# LPC_LCD_V098_0.net
KiCad netlist of a schematic drawn in EAGLE
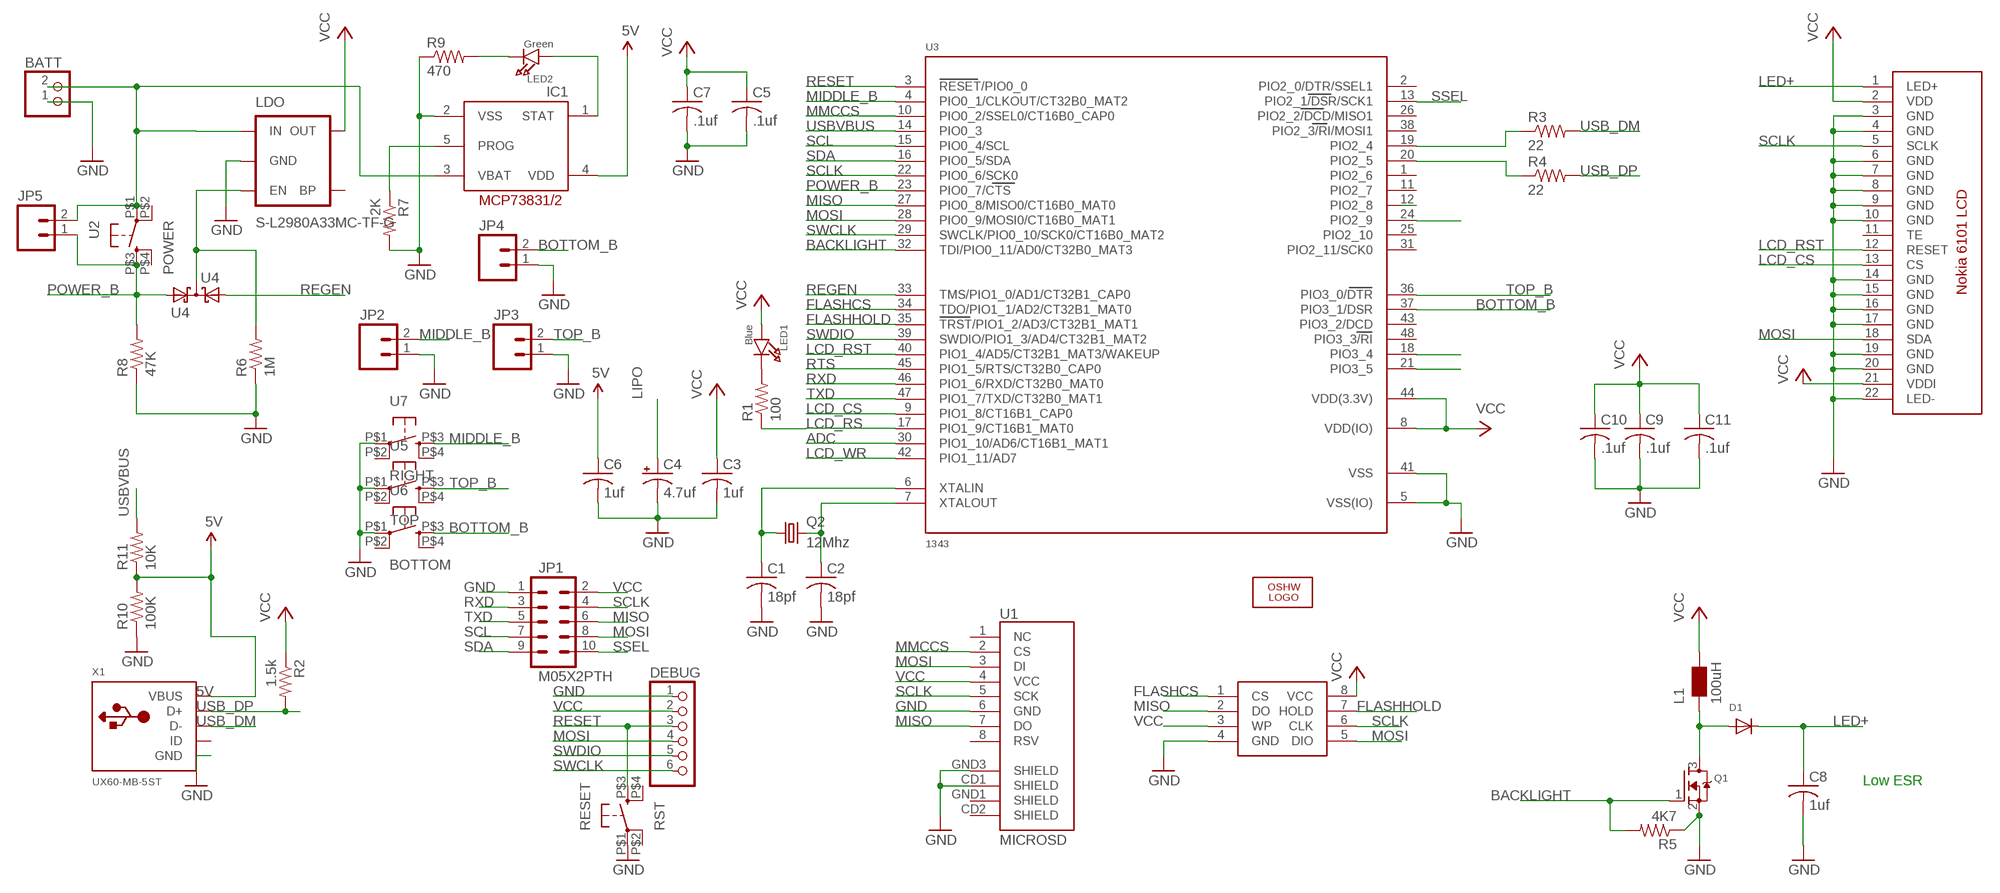
[diagram p0: schematic, sheet 1]

(export (version "E")
  (design (tool "Eeschema 10.0.6"))
  (components
    (comp (ref "BATT")
      (value "JST_2PIN-SMT")
      (footprint "eagle-import:JST-PH-2-SMT")
      (libsource (lib "eagle-import") (part "JST_2PIN-SMT"))
    )
    (comp (ref "C1")
      (value "18pf")
      (footprint "eagle-import:C0805")
      (libsource (lib "eagle-import") (part "C-USC0805"))
    )
    (comp (ref "C2")
      (value "18pf")
      (footprint "eagle-import:C0805")
      (libsource (lib "eagle-import") (part "C-USC0805"))
    )
    (comp (ref "C3")
      (value "1uf")
      (footprint "eagle-import:C0805")
      (libsource (lib "eagle-import") (part "C-USC0805"))
    )
    (comp (ref "C4")
      (value "4.7uf")
      (footprint "eagle-import:EIA3216")
      (libsource (lib "eagle-import") (part "CAP_POL1206"))
    )
    (comp (ref "C5")
      (value ".1uf")
      (footprint "eagle-import:C0805")
      (libsource (lib "eagle-import") (part "C-USC0805"))
    )
    (comp (ref "C6")
      (value "1uf")
      (footprint "eagle-import:C0805")
      (libsource (lib "eagle-import") (part "C-USC0805"))
    )
    (comp (ref "C7")
      (value ".1uf")
      (footprint "eagle-import:C0805")
      (libsource (lib "eagle-import") (part "C-USC0805"))
    )
    (comp (ref "C8")
      (value "1uf")
      (footprint "eagle-import:C0805")
      (libsource (lib "eagle-import") (part "C-USC0805"))
    )
    (comp (ref "C9")
      (value ".1uf")
      (footprint "eagle-import:C0805")
      (libsource (lib "eagle-import") (part "C-USC0805"))
    )
    (comp (ref "C10")
      (value ".1uf")
      (footprint "eagle-import:C0805")
      (libsource (lib "eagle-import") (part "C-USC0805"))
    )
    (comp (ref "C11")
      (value ".1uf")
      (footprint "eagle-import:C0805")
      (libsource (lib "eagle-import") (part "C-USC0805"))
    )
    (comp (ref "D1")
      (value "DIODESOD-123")
      (footprint "eagle-import:SOD-123")
      (libsource (lib "eagle-import") (part "DIODESOD-123"))
    )
    (comp (ref "DEBUG")
      (value "HEADER-1X6ROUND")
      (footprint "eagle-import:1X06_ROUND")
      (libsource (lib "eagle-import") (part "HEADER-1X6ROUND"))
    )
    (comp (ref "IC1")
      (value "MCP73831")
      (footprint "eagle-import:SOT23-5L")
      (libsource (lib "eagle-import") (part "MCP73831/OT"))
    )
    (comp (ref "JP1")
      (value "M05X2PTH")
      (footprint "eagle-import:AVR_ICSP")
      (libsource (lib "eagle-import") (part "M05X2PTH"))
    )
    (comp (ref "JP2")
      (value "M02LOCK")
      (footprint "eagle-import:1X02_LOCK")
      (libsource (lib "eagle-import") (part "M02LOCK"))
    )
    (comp (ref "JP3")
      (value "M02LOCK")
      (footprint "eagle-import:1X02_LOCK")
      (libsource (lib "eagle-import") (part "M02LOCK"))
    )
    (comp (ref "JP4")
      (value "M02LOCK")
      (footprint "eagle-import:1X02_LOCK")
      (libsource (lib "eagle-import") (part "M02LOCK"))
    )
    (comp (ref "JP5")
      (value "M02LOCK")
      (footprint "eagle-import:1X02_LOCK")
      (libsource (lib "eagle-import") (part "M02LOCK"))
    )
    (comp (ref "L1")
      (value "100uH")
      (footprint "eagle-import:WE-KI_1008_B")
      (libsource (lib "eagle-import") (part "WE-KIHQ_1008"))
    )
    (comp (ref "LDO")
      (value "S-L2980A33MC-TF-G")
      (footprint "eagle-import:SOT23-5")
      (libsource (lib "eagle-import") (part "V_REG_LDOSMD"))
    )
    (comp (ref "LED1")
      (value "Blue")
      (footprint "eagle-import:CHIPLED_0805")
      (libsource (lib "eagle-import") (part "LED0805"))
    )
    (comp (ref "LED2")
      (value "Green")
      (footprint "eagle-import:CHIPLED_0805")
      (libsource (lib "eagle-import") (part "LED0805"))
    )
    (comp (ref "LOGO1")
      (value "OSHW_LOGO_FILLX0350-NT")
      (footprint "eagle-import:OSHW_FILLX350_NOTEXT")
      (libsource (lib "eagle-import") (part "OSHW_LOGO_FILLX0350-NT"))
    )
    (comp (ref "Q1")
      (value "MOSFET-NREFLOW")
      (footprint "eagle-import:SOT23-R")
      (libsource (lib "eagle-import") (part "MOSFET-NREFLOW"))
    )
    (comp (ref "Q2")
      (value "12Mhz")
      (footprint "eagle-import:CRYSTAL-SMD-5X3")
      (libsource (lib "eagle-import") (part "CRYSTAL5X3"))
    )
    (comp (ref "R1")
      (value "100")
      (footprint "eagle-import:M0805")
      (libsource (lib "eagle-import") (part "R-US_M0805"))
    )
    (comp (ref "R2")
      (value "1.5k")
      (footprint "eagle-import:M0805")
      (libsource (lib "eagle-import") (part "R-US_M0805"))
    )
    (comp (ref "R3")
      (value "22")
      (footprint "eagle-import:M0805")
      (libsource (lib "eagle-import") (part "R-US_M0805"))
    )
    (comp (ref "R4")
      (value "22")
      (footprint "eagle-import:M0805")
      (libsource (lib "eagle-import") (part "R-US_M0805"))
    )
    (comp (ref "R5")
      (value "4K7")
      (footprint "eagle-import:M0805")
      (libsource (lib "eagle-import") (part "R-US_M0805"))
    )
    (comp (ref "R6")
      (value "1M")
      (footprint "eagle-import:M0805")
      (libsource (lib "eagle-import") (part "R-US_M0805"))
    )
    (comp (ref "R7")
      (value "2K")
      (footprint "eagle-import:M0805")
      (libsource (lib "eagle-import") (part "R-US_M0805"))
    )
    (comp (ref "R8")
      (value "47K")
      (footprint "eagle-import:M0805")
      (libsource (lib "eagle-import") (part "R-US_M0805"))
    )
    (comp (ref "R9")
      (value "470")
      (footprint "eagle-import:M0805")
      (libsource (lib "eagle-import") (part "R-US_M0805"))
    )
    (comp (ref "R10")
      (value "100K")
      (footprint "eagle-import:M0805")
      (libsource (lib "eagle-import") (part "R-US_M0805"))
    )
    (comp (ref "R11")
      (value "10K")
      (footprint "eagle-import:M0805")
      (libsource (lib "eagle-import") (part "R-US_M0805"))
    )
    (comp (ref "RESET")
      (value "RST")
      (footprint "eagle-import:SWITCH_KMR4")
      (libsource (lib "eagle-import") (part "SWITCH_KMR4"))
    )
    (comp (ref "U$1")
      (value "spiflash")
      (footprint "eagle-import:SOIC8")
      (libsource (lib "eagle-import") (part "SPIFLASH"))
    )
    (comp (ref "U$3")
      (value "PETERATMEGA644_NOKIA6101_LCD")
      (footprint "eagle-import:PETERATMEGA644_NOKIA6101_LCD")
      (libsource (lib "eagle-import") (part "PETERATMEGA644_NOKIA6101_LCD"))
    )
    (comp (ref "U1")
      (value "MICROSD")
      (footprint "eagle-import:MICRO-SD-SOCKET-PP")
      (libsource (lib "eagle-import") (part "USD-SOCKETNEW"))
    )
    (comp (ref "U2")
      (value "POWER")
      (footprint "eagle-import:SWITCH_KMS_WIDE")
      (libsource (lib "eagle-import") (part "KMS_SWITCHSWITCH_KMS_WIDE_HAND"))
    )
    (comp (ref "U3")
      (value "1343")
      (footprint "eagle-import:LQFP48")
      (fields (field (name "MANF") "NXP"))
      (libsource (lib "eagle-import") (part "LPC1113/4"))
    )
    (comp (ref "U4")
      (value "U4")
      (footprint "eagle-import:SOT23")
      (libsource (lib "eagle-import") (part "BAT54CWT1G"))
    )
    (comp (ref "U5")
      (value "TOP")
      (footprint "eagle-import:SWITCH_KMS_WIDE")
      (libsource (lib "eagle-import") (part "KMS_SWITCHSWITCH_KMS_WIDE_HAND"))
    )
    (comp (ref "U6")
      (value "BOTTOM")
      (footprint "eagle-import:SWITCH_KMS_WIDE")
      (libsource (lib "eagle-import") (part "KMS_SWITCHSWITCH_KMS_WIDE_HAND"))
    )
    (comp (ref "U7")
      (value "RIGHT")
      (footprint "eagle-import:SWITCH_KMS_WIDE")
      (libsource (lib "eagle-import") (part "KMS_SWITCHSWITCH_KMS_WIDE_HAND"))
    )
    (comp (ref "X1")
      (value "UX60-MB-5ST")
      (footprint "eagle-import:USB-MINIB")
      (libsource (lib "eagle-import") (part "USBMINIB"))
    )
  )
  (nets
    (net (code "1") (name "/ADC") (class "Default")
      (node (ref "U3") (pin "30") (pinfunction "PIO1_10/AD6/CT16B1_MAT1_30") (pintype "bidirectional"))
    )
    (net (code "2") (name "/BACKLIGHT") (class "Default")
      (node (ref "Q1") (pin "1") (pinfunction "G_1") (pintype "bidirectional"))
      (node (ref "R5") (pin "2") (pinfunction "2_2") (pintype "passive"))
      (node (ref "U3") (pin "32") (pinfunction "TDI/PIO0_11/AD0/CT32B0_MAT3_32") (pintype "bidirectional"))
    )
    (net (code "3") (name "/BOTTOM_B") (class "Default")
      (node (ref "JP4") (pin "2") (pinfunction "2_2") (pintype "passive"))
      (node (ref "U3") (pin "37") (pinfunction "PIO3_1/DSR_37") (pintype "bidirectional"))
      (node (ref "U6") (pin "P$3") (pinfunction "3_P$3") (pintype "passive"))
    )
    (net (code "4") (name "/FLASHCS") (class "Default")
      (node (ref "U$1") (pin "1") (pinfunction "CS_1") (pintype "bidirectional"))
      (node (ref "U3") (pin "34") (pinfunction "TDO/PIO1_1/AD2/CT32B1_MAT0_34") (pintype "bidirectional"))
    )
    (net (code "5") (name "/FLASHHOLD") (class "Default")
      (node (ref "U$1") (pin "7") (pinfunction "HOLD_7") (pintype "bidirectional"))
      (node (ref "U3") (pin "35") (pinfunction "TRST/PIO1_2/AD3/CT32B1_MAT1_35") (pintype "bidirectional"))
    )
    (net (code "6") (name "/LCD_CS") (class "Default")
      (node (ref "U$3") (pin "13") (pinfunction "CS_13") (pintype "bidirectional"))
      (node (ref "U3") (pin "9") (pinfunction "PIO1_8/CT16B1_CAP0_9") (pintype "bidirectional"))
    )
    (net (code "7") (name "/LCD_RS") (class "Default")
      (node (ref "R1") (pin "1") (pinfunction "1_1") (pintype "passive"))
      (node (ref "U3") (pin "17") (pinfunction "PIO1_9/CT16B1_MAT0_17") (pintype "bidirectional"))
    )
    (net (code "8") (name "/LCD_RST") (class "Default")
      (node (ref "U$3") (pin "12") (pinfunction "RESET_12") (pintype "bidirectional"))
      (node (ref "U3") (pin "40") (pinfunction "PIO1_4/AD5/CT32B1_MAT3/WAKEUP_40") (pintype "bidirectional"))
    )
    (net (code "9") (name "/LCD_WR") (class "Default")
      (node (ref "U3") (pin "42") (pinfunction "PIO1_11/AD7_42") (pintype "bidirectional"))
    )
    (net (code "10") (name "/LED+") (class "Default")
      (node (ref "C8") (pin "1") (pinfunction "1_1") (pintype "passive"))
      (node (ref "D1") (pin "C") (pinfunction "C_C") (pintype "passive"))
      (node (ref "U$3") (pin "1") (pinfunction "LED+_1") (pintype "bidirectional"))
    )
    (net (code "11") (name "/LIPO") (class "Default")
      (node (ref "BATT") (pin "2") (pinfunction "1_2") (pintype "passive"))
      (node (ref "C4") (pin "A") (pinfunction "+_A") (pintype "passive"))
      (node (ref "IC1") (pin "3") (pinfunction "VBAT_3") (pintype "bidirectional"))
      (node (ref "JP5") (pin "2") (pinfunction "2_2") (pintype "passive"))
      (node (ref "LDO") (pin "1") (pinfunction "IN_1") (pintype "input"))
      (node (ref "U2") (pin "P$1") (pinfunction "1_P$1") (pintype "passive"))
    )
    (net (code "12") (name "/MIDDLE_B") (class "Default")
      (node (ref "JP2") (pin "2") (pinfunction "2_2") (pintype "passive"))
      (node (ref "U3") (pin "4") (pinfunction "PIO0_1/CLKOUT/CT32B0_MAT2_4") (pintype "bidirectional"))
      (node (ref "U7") (pin "P$3") (pinfunction "3_P$3") (pintype "passive"))
    )
    (net (code "13") (name "/MISO") (class "Default")
      (node (ref "JP1") (pin "6") (pinfunction "6_6") (pintype "passive"))
      (node (ref "U$1") (pin "2") (pinfunction "DO_2") (pintype "bidirectional"))
      (node (ref "U1") (pin "7") (pinfunction "DO_7") (pintype "bidirectional"))
      (node (ref "U3") (pin "27") (pinfunction "PIO0_8/MISO0/CT16B0_MAT0_27") (pintype "bidirectional"))
    )
    (net (code "14") (name "/MMCCS") (class "Default")
      (node (ref "U1") (pin "2") (pinfunction "CS_2") (pintype "bidirectional"))
      (node (ref "U3") (pin "10") (pinfunction "PIO0_2/SSEL0/CT16B0_CAP0_10") (pintype "bidirectional"))
    )
    (net (code "15") (name "/MOSI") (class "Default")
      (node (ref "DEBUG") (pin "4") (pinfunction "4_4") (pintype "passive"))
      (node (ref "JP1") (pin "8") (pinfunction "8_8") (pintype "passive"))
      (node (ref "U$1") (pin "5") (pinfunction "DIO_5") (pintype "bidirectional"))
      (node (ref "U$3") (pin "18") (pinfunction "SDA_18") (pintype "bidirectional"))
      (node (ref "U1") (pin "3") (pinfunction "DI_3") (pintype "bidirectional"))
      (node (ref "U3") (pin "28") (pinfunction "PIO0_9/MOSI0/CT16B0_MAT1_28") (pintype "bidirectional"))
    )
    (net (code "16") (name "/POWER_B") (class "Default")
      (node (ref "JP5") (pin "1") (pinfunction "1_1") (pintype "passive"))
      (node (ref "R8") (pin "2") (pinfunction "2_2") (pintype "passive"))
      (node (ref "U2") (pin "P$3") (pinfunction "3_P$3") (pintype "passive"))
      (node (ref "U3") (pin "23") (pinfunction "PIO0_7/CTS_23") (pintype "bidirectional"))
      (node (ref "U4") (pin "2") (pinfunction "K1_2") (pintype "passive"))
    )
    (net (code "17") (name "/REGEN") (class "Default")
      (node (ref "U3") (pin "33") (pinfunction "TMS/PIO1_0/AD1/CT32B1_CAP0_33") (pintype "bidirectional"))
      (node (ref "U4") (pin "1") (pinfunction "K2_1") (pintype "passive"))
    )
    (net (code "18") (name "/RESET") (class "Default")
      (node (ref "DEBUG") (pin "3") (pinfunction "3_3") (pintype "passive"))
      (node (ref "RESET") (pin "P$3") (pinfunction "3_P$3") (pintype "passive"))
      (node (ref "U3") (pin "3") (pinfunction "RESET/PIO0_0_3") (pintype "bidirectional"))
    )
    (net (code "19") (name "/RTS") (class "Default")
      (node (ref "U3") (pin "45") (pinfunction "PIO1_5/RTS/CT32B0_CAP0_45") (pintype "bidirectional"))
    )
    (net (code "20") (name "/RXD") (class "Default")
      (node (ref "JP1") (pin "3") (pinfunction "3_3") (pintype "passive"))
      (node (ref "U3") (pin "46") (pinfunction "PIO1_6/RXD/CT32B0_MAT0_46") (pintype "bidirectional"))
    )
    (net (code "21") (name "/SCL") (class "Default")
      (node (ref "JP1") (pin "7") (pinfunction "7_7") (pintype "passive"))
      (node (ref "U3") (pin "15") (pinfunction "PIO0_4/SCL_15") (pintype "bidirectional"))
    )
    (net (code "22") (name "/SCLK") (class "Default")
      (node (ref "JP1") (pin "4") (pinfunction "4_4") (pintype "passive"))
      (node (ref "U$1") (pin "6") (pinfunction "CLK_6") (pintype "bidirectional"))
      (node (ref "U$3") (pin "5") (pinfunction "SCLK_5") (pintype "bidirectional"))
      (node (ref "U1") (pin "5") (pinfunction "SCK_5") (pintype "bidirectional"))
      (node (ref "U3") (pin "22") (pinfunction "PIO0_6/SCK0_22") (pintype "bidirectional"))
    )
    (net (code "23") (name "/SDA") (class "Default")
      (node (ref "JP1") (pin "9") (pinfunction "9_9") (pintype "passive"))
      (node (ref "U3") (pin "16") (pinfunction "PIO0_5/SDA_16") (pintype "bidirectional"))
    )
    (net (code "24") (name "/SSEL") (class "Default")
      (node (ref "JP1") (pin "10") (pinfunction "10_10") (pintype "passive"))
      (node (ref "U3") (pin "13") (pinfunction "PIO2_1/DSR/SCK1_13") (pintype "bidirectional"))
    )
    (net (code "25") (name "/SWCLK") (class "Default")
      (node (ref "DEBUG") (pin "6") (pinfunction "6_6") (pintype "passive"))
      (node (ref "U3") (pin "29") (pinfunction "SWCLK/PIO0_10/SCK0/CT16B0_MAT2_29") (pintype "bidirectional"))
    )
    (net (code "26") (name "/SWDIO") (class "Default")
      (node (ref "DEBUG") (pin "5") (pinfunction "5_5") (pintype "passive"))
      (node (ref "U3") (pin "39") (pinfunction "SWDIO/PIO1_3/AD4/CT32B1_MAT2_39") (pintype "bidirectional"))
    )
    (net (code "27") (name "/TOP_B") (class "Default")
      (node (ref "JP3") (pin "2") (pinfunction "2_2") (pintype "passive"))
      (node (ref "U3") (pin "36") (pinfunction "PIO3_0/DTR_36") (pintype "bidirectional"))
      (node (ref "U5") (pin "P$3") (pinfunction "3_P$3") (pintype "passive"))
    )
    (net (code "28") (name "/TXD") (class "Default")
      (node (ref "JP1") (pin "5") (pinfunction "5_5") (pintype "passive"))
      (node (ref "U3") (pin "47") (pinfunction "PIO1_7/TXD/CT32B0_MAT1_47") (pintype "bidirectional"))
    )
    (net (code "29") (name "/USBVBUS") (class "Default")
      (node (ref "R11") (pin "2") (pinfunction "2_2") (pintype "passive"))
      (node (ref "U3") (pin "14") (pinfunction "PIO0_3_14") (pintype "bidirectional"))
    )
    (net (code "30") (name "/USB_DM") (class "Default")
      (node (ref "R3") (pin "2") (pinfunction "2_2") (pintype "passive"))
      (node (ref "X1") (pin "D-") (pinfunction "D-_D-") (pintype "bidirectional"))
    )
    (net (code "31") (name "/USB_DP") (class "Default")
      (node (ref "R2") (pin "2") (pinfunction "2_2") (pintype "passive"))
      (node (ref "R4") (pin "2") (pinfunction "2_2") (pintype "passive"))
      (node (ref "X1") (pin "D+") (pinfunction "D+_D+") (pintype "bidirectional"))
    )
    (net (code "32") (name "5V") (class "Default")
      (node (ref "C6") (pin "1") (pinfunction "1_1") (pintype "passive"))
      (node (ref "IC1") (pin "4") (pinfunction "VDD_4") (pintype "power_in"))
      (node (ref "R10") (pin "2") (pinfunction "2_2") (pintype "passive"))
      (node (ref "R11") (pin "1") (pinfunction "1_1") (pintype "passive"))
      (node (ref "X1") (pin "VBUS") (pinfunction "VBUS_VBUS") (pintype "power_in"))
    )
    (net (code "33") (name "GND") (class "Default")
      (node (ref "BATT") (pin "1") (pinfunction "2_1") (pintype "passive"))
      (node (ref "C1") (pin "2") (pinfunction "2_2") (pintype "passive"))
      (node (ref "C10") (pin "2") (pinfunction "2_2") (pintype "passive"))
      (node (ref "C11") (pin "2") (pinfunction "2_2") (pintype "passive"))
      (node (ref "C2") (pin "2") (pinfunction "2_2") (pintype "passive"))
      (node (ref "C3") (pin "2") (pinfunction "2_2") (pintype "passive"))
      (node (ref "C4") (pin "C") (pinfunction "-_C") (pintype "passive"))
      (node (ref "C5") (pin "2") (pinfunction "2_2") (pintype "passive"))
      (node (ref "C6") (pin "2") (pinfunction "2_2") (pintype "passive"))
      (node (ref "C7") (pin "2") (pinfunction "2_2") (pintype "passive"))
      (node (ref "C8") (pin "2") (pinfunction "2_2") (pintype "passive"))
      (node (ref "C9") (pin "2") (pinfunction "2_2") (pintype "passive"))
      (node (ref "DEBUG") (pin "1") (pinfunction "1_1") (pintype "passive"))
      (node (ref "IC1") (pin "2") (pinfunction "VSS_2") (pintype "power_in"))
      (node (ref "JP1") (pin "1") (pinfunction "1_1") (pintype "passive"))
      (node (ref "JP2") (pin "1") (pinfunction "1_1") (pintype "passive"))
      (node (ref "JP3") (pin "1") (pinfunction "1_1") (pintype "passive"))
      (node (ref "JP4") (pin "1") (pinfunction "1_1") (pintype "passive"))
      (node (ref "LDO") (pin "2") (pinfunction "GND_2") (pintype "input"))
      (node (ref "Q1") (pin "2") (pinfunction "S_2") (pintype "bidirectional"))
      (node (ref "R10") (pin "1") (pinfunction "1_1") (pintype "passive"))
      (node (ref "R5") (pin "1") (pinfunction "1_1") (pintype "passive"))
      (node (ref "R6") (pin "1") (pinfunction "1_1") (pintype "passive"))
      (node (ref "R7") (pin "2") (pinfunction "2_2") (pintype "passive"))
      (node (ref "R8") (pin "1") (pinfunction "1_1") (pintype "passive"))
      (node (ref "R9") (pin "1") (pinfunction "1_1") (pintype "passive"))
      (node (ref "RESET") (pin "P$1") (pinfunction "1_P$1") (pintype "passive"))
      (node (ref "U$1") (pin "4") (pinfunction "GND_4") (pintype "bidirectional"))
      (node (ref "U$3") (pin "10") (pinfunction "GND_10") (pintype "bidirectional"))
      (node (ref "U$3") (pin "14") (pinfunction "GND_14") (pintype "bidirectional"))
      (node (ref "U$3") (pin "15") (pinfunction "GND_15") (pintype "bidirectional"))
      (node (ref "U$3") (pin "16") (pinfunction "GND_16") (pintype "bidirectional"))
      (node (ref "U$3") (pin "17") (pinfunction "GND_17") (pintype "bidirectional"))
      (node (ref "U$3") (pin "19") (pinfunction "GND_19") (pintype "bidirectional"))
      (node (ref "U$3") (pin "20") (pinfunction "GND_20") (pintype "bidirectional"))
      (node (ref "U$3") (pin "22") (pinfunction "LED-_22") (pintype "bidirectional"))
      (node (ref "U$3") (pin "3") (pinfunction "GND_3") (pintype "bidirectional"))
      (node (ref "U$3") (pin "4") (pinfunction "GND_4") (pintype "bidirectional"))
      (node (ref "U$3") (pin "6") (pinfunction "GND_6") (pintype "bidirectional"))
      (node (ref "U$3") (pin "7") (pinfunction "GND_7") (pintype "bidirectional"))
      (node (ref "U$3") (pin "8") (pinfunction "GND_8") (pintype "bidirectional"))
      (node (ref "U$3") (pin "9") (pinfunction "GND_9") (pintype "bidirectional"))
      (node (ref "U1") (pin "6") (pinfunction "GND_6") (pintype "bidirectional"))
      (node (ref "U1") (pin "CD1") (pinfunction "SHIELD_CD1") (pintype "bidirectional"))
      (node (ref "U1") (pin "GND3") (pinfunction "SHIELD_GND3") (pintype "bidirectional"))
      (node (ref "U3") (pin "41") (pinfunction "VSS_41") (pintype "power_in"))
      (node (ref "U3") (pin "5") (pinfunction "VSS(IO)_5") (pintype "power_in"))
      (node (ref "U5") (pin "P$1") (pinfunction "1_P$1") (pintype "passive"))
      (node (ref "U6") (pin "P$1") (pinfunction "1_P$1") (pintype "passive"))
      (node (ref "U7") (pin "P$1") (pinfunction "1_P$1") (pintype "passive"))
      (node (ref "X1") (pin "GND") (pinfunction "GND_GND") (pintype "power_in"))
    )
    (net (code "34") (name "Net-(IC1-PROG)") (class "Default")
      (node (ref "IC1") (pin "5") (pinfunction "PROG_5") (pintype "input"))
      (node (ref "R7") (pin "1") (pinfunction "1_1") (pintype "passive"))
    )
    (net (code "35") (name "Net-(IC1-STAT)") (class "Default")
      (node (ref "IC1") (pin "1") (pinfunction "STAT_1") (pintype "output"))
      (node (ref "LED2") (pin "A") (pinfunction "A_A") (pintype "passive"))
    )
    (net (code "36") (name "Net-(L1-1)") (class "Default")
      (node (ref "D1") (pin "A") (pinfunction "A_A") (pintype "passive"))
      (node (ref "L1") (pin "2") (pinfunction "1_2") (pintype "passive"))
      (node (ref "Q1") (pin "3") (pinfunction "D_3") (pintype "bidirectional"))
    )
    (net (code "37") (name "Net-(LDO-EN)") (class "Default")
      (node (ref "LDO") (pin "3") (pinfunction "EN_3") (pintype "input"))
      (node (ref "R6") (pin "2") (pinfunction "2_2") (pintype "passive"))
      (node (ref "U4") (pin "3") (pinfunction "AA_3") (pintype "passive"))
    )
    (net (code "38") (name "Net-(LED1-PadC)") (class "Default")
      (node (ref "LED1") (pin "C") (pinfunction "C_C") (pintype "passive"))
      (node (ref "R1") (pin "2") (pinfunction "2_2") (pintype "passive"))
    )
    (net (code "39") (name "Net-(LED2-PadC)") (class "Default")
      (node (ref "LED2") (pin "C") (pinfunction "C_C") (pintype "passive"))
      (node (ref "R9") (pin "2") (pinfunction "2_2") (pintype "passive"))
    )
    (net (code "40") (name "Net-(Q2-2)") (class "Default")
      (node (ref "C2") (pin "1") (pinfunction "1_1") (pintype "passive"))
      (node (ref "Q2") (pin "3") (pinfunction "2_3") (pintype "passive"))
      (node (ref "U3") (pin "7") (pinfunction "XTALOUT_7") (pintype "output"))
    )
    (net (code "41") (name "Net-(U3-PIO2_4)") (class "Default")
      (node (ref "R3") (pin "1") (pinfunction "1_1") (pintype "passive"))
      (node (ref "U3") (pin "19") (pinfunction "PIO2_4_19") (pintype "bidirectional"))
    )
    (net (code "42") (name "Net-(U3-PIO2_5)") (class "Default")
      (node (ref "R4") (pin "1") (pinfunction "1_1") (pintype "passive"))
      (node (ref "U3") (pin "20") (pinfunction "PIO2_5_20") (pintype "bidirectional"))
    )
    (net (code "43") (name "Net-(U3-XTALIN)") (class "Default")
      (node (ref "C1") (pin "1") (pinfunction "1_1") (pintype "passive"))
      (node (ref "Q2") (pin "1") (pinfunction "1_1") (pintype "passive"))
      (node (ref "U3") (pin "6") (pinfunction "XTALIN_6") (pintype "input"))
    )
    (net (code "44") (name "VCC") (class "Default")
      (node (ref "C10") (pin "1") (pinfunction "1_1") (pintype "passive"))
      (node (ref "C11") (pin "1") (pinfunction "1_1") (pintype "passive"))
      (node (ref "C3") (pin "1") (pinfunction "1_1") (pintype "passive"))
      (node (ref "C5") (pin "1") (pinfunction "1_1") (pintype "passive"))
      (node (ref "C7") (pin "1") (pinfunction "1_1") (pintype "passive"))
      (node (ref "C9") (pin "1") (pinfunction "1_1") (pintype "passive"))
      (node (ref "DEBUG") (pin "2") (pinfunction "2_2") (pintype "passive"))
      (node (ref "JP1") (pin "2") (pinfunction "2_2") (pintype "passive"))
      (node (ref "L1") (pin "1") (pinfunction "2_1") (pintype "passive"))
      (node (ref "LDO") (pin "5") (pinfunction "OUT_5") (pintype "passive"))
      (node (ref "LED1") (pin "A") (pinfunction "A_A") (pintype "passive"))
      (node (ref "R2") (pin "1") (pinfunction "1_1") (pintype "passive"))
      (node (ref "U$1") (pin "3") (pinfunction "WP_3") (pintype "bidirectional"))
      (node (ref "U$1") (pin "8") (pinfunction "VCC_8") (pintype "bidirectional"))
      (node (ref "U$3") (pin "2") (pinfunction "VDD_2") (pintype "bidirectional"))
      (node (ref "U$3") (pin "21") (pinfunction "VDDI_21") (pintype "bidirectional"))
      (node (ref "U1") (pin "4") (pinfunction "VCC_4") (pintype "bidirectional"))
      (node (ref "U3") (pin "44") (pinfunction "VDD(3.3V)_44") (pintype "power_in"))
      (node (ref "U3") (pin "8") (pinfunction "VDD(IO)_8") (pintype "power_in"))
    )
    (net (code "45") (name "unconnected-(LDO-BP-Pad4)") (class "Default")
      (node (ref "LDO") (pin "4") (pinfunction "BP_4") (pintype "no_connect"))
    )
    (net (code "46") (name "unconnected-(RESET-2-PadP$2)") (class "Default")
      (node (ref "RESET") (pin "P$2") (pinfunction "2_P$2") (pintype "passive"))
    )
    (net (code "47") (name "unconnected-(RESET-4-PadP$4)") (class "Default")
      (node (ref "RESET") (pin "P$4") (pinfunction "4_P$4") (pintype "passive"))
    )
    (net (code "48") (name "unconnected-(U$3-TE-Pad11)") (class "Default")
      (node (ref "U$3") (pin "11") (pinfunction "TE_11") (pintype "bidirectional"))
    )
    (net (code "49") (name "unconnected-(U1-NC-Pad1)") (class "Default")
      (node (ref "U1") (pin "1") (pinfunction "NC_1") (pintype "bidirectional"))
    )
    (net (code "50") (name "unconnected-(U1-RSV-Pad8)") (class "Default")
      (node (ref "U1") (pin "8") (pinfunction "RSV_8") (pintype "bidirectional"))
    )
    (net (code "51") (name "unconnected-(U1-SHIELD-PadCD2)") (class "Default")
      (node (ref "U1") (pin "CD2") (pinfunction "SHIELD_CD2") (pintype "bidirectional"))
    )
    (net (code "52") (name "unconnected-(U1-SHIELD-PadGND1)") (class "Default")
      (node (ref "U1") (pin "GND1") (pinfunction "SHIELD_GND1") (pintype "bidirectional"))
    )
    (net (code "53") (name "unconnected-(U2-2-PadP$2)") (class "Default")
      (node (ref "U2") (pin "P$2") (pinfunction "2_P$2") (pintype "passive"))
    )
    (net (code "54") (name "unconnected-(U2-4-PadP$4)") (class "Default")
      (node (ref "U2") (pin "P$4") (pinfunction "4_P$4") (pintype "passive"))
    )
    (net (code "55") (name "unconnected-(U3-PIO2_0{slash}DTR{slash}SSEL1-Pad2)") (class "Default")
      (node (ref "U3") (pin "2") (pinfunction "PIO2_0/DTR/SSEL1_2") (pintype "bidirectional"))
    )
    (net (code "56") (name "unconnected-(U3-PIO2_2{slash}DCD{slash}MISO1-Pad26)") (class "Default")
      (node (ref "U3") (pin "26") (pinfunction "PIO2_2/DCD/MISO1_26") (pintype "bidirectional"))
    )
    (net (code "57") (name "unconnected-(U3-PIO2_3{slash}RI{slash}MOSI1-Pad38)") (class "Default")
      (node (ref "U3") (pin "38") (pinfunction "PIO2_3/RI/MOSI1_38") (pintype "bidirectional"))
    )
    (net (code "58") (name "unconnected-(U3-PIO2_6-Pad1)") (class "Default")
      (node (ref "U3") (pin "1") (pinfunction "PIO2_6_1") (pintype "bidirectional"))
    )
    (net (code "59") (name "unconnected-(U3-PIO2_7-Pad11)") (class "Default")
      (node (ref "U3") (pin "11") (pinfunction "PIO2_7_11") (pintype "bidirectional"))
    )
    (net (code "60") (name "unconnected-(U3-PIO2_8-Pad12)") (class "Default")
      (node (ref "U3") (pin "12") (pinfunction "PIO2_8_12") (pintype "bidirectional"))
    )
    (net (code "61") (name "unconnected-(U3-PIO2_9-Pad24)") (class "Default")
      (node (ref "U3") (pin "24") (pinfunction "PIO2_9_24") (pintype "bidirectional"))
    )
    (net (code "62") (name "unconnected-(U3-PIO2_10-Pad25)") (class "Default")
      (node (ref "U3") (pin "25") (pinfunction "PIO2_10_25") (pintype "bidirectional"))
    )
    (net (code "63") (name "unconnected-(U3-PIO2_11{slash}SCK0-Pad31)") (class "Default")
      (node (ref "U3") (pin "31") (pinfunction "PIO2_11/SCK0_31") (pintype "bidirectional"))
    )
    (net (code "64") (name "unconnected-(U3-PIO3_2{slash}DCD-Pad43)") (class "Default")
      (node (ref "U3") (pin "43") (pinfunction "PIO3_2/DCD_43") (pintype "bidirectional"))
    )
    (net (code "65") (name "unconnected-(U3-PIO3_3{slash}RI-Pad48)") (class "Default")
      (node (ref "U3") (pin "48") (pinfunction "PIO3_3/RI_48") (pintype "bidirectional"))
    )
    (net (code "66") (name "unconnected-(U3-PIO3_4-Pad18)") (class "Default")
      (node (ref "U3") (pin "18") (pinfunction "PIO3_4_18") (pintype "bidirectional"))
    )
    (net (code "67") (name "unconnected-(U3-PIO3_5-Pad21)") (class "Default")
      (node (ref "U3") (pin "21") (pinfunction "PIO3_5_21") (pintype "bidirectional"))
    )
    (net (code "68") (name "unconnected-(U5-2-PadP$2)") (class "Default")
      (node (ref "U5") (pin "P$2") (pinfunction "2_P$2") (pintype "passive"))
    )
    (net (code "69") (name "unconnected-(U5-4-PadP$4)") (class "Default")
      (node (ref "U5") (pin "P$4") (pinfunction "4_P$4") (pintype "passive"))
    )
    (net (code "70") (name "unconnected-(U6-2-PadP$2)") (class "Default")
      (node (ref "U6") (pin "P$2") (pinfunction "2_P$2") (pintype "passive"))
    )
    (net (code "71") (name "unconnected-(U6-4-PadP$4)") (class "Default")
      (node (ref "U6") (pin "P$4") (pinfunction "4_P$4") (pintype "passive"))
    )
    (net (code "72") (name "unconnected-(U7-2-PadP$2)") (class "Default")
      (node (ref "U7") (pin "P$2") (pinfunction "2_P$2") (pintype "passive"))
    )
    (net (code "73") (name "unconnected-(U7-4-PadP$4)") (class "Default")
      (node (ref "U7") (pin "P$4") (pinfunction "4_P$4") (pintype "passive"))
    )
    (net (code "74") (name "unconnected-(X1-PadID)") (class "Default")
      (node (ref "X1") (pin "ID") (pinfunction "ID_ID") (pintype "bidirectional"))
    )
  )
)
